# MySens-easyRS485-v001.net
KiCad netlist of a schematic drawn in EAGLE
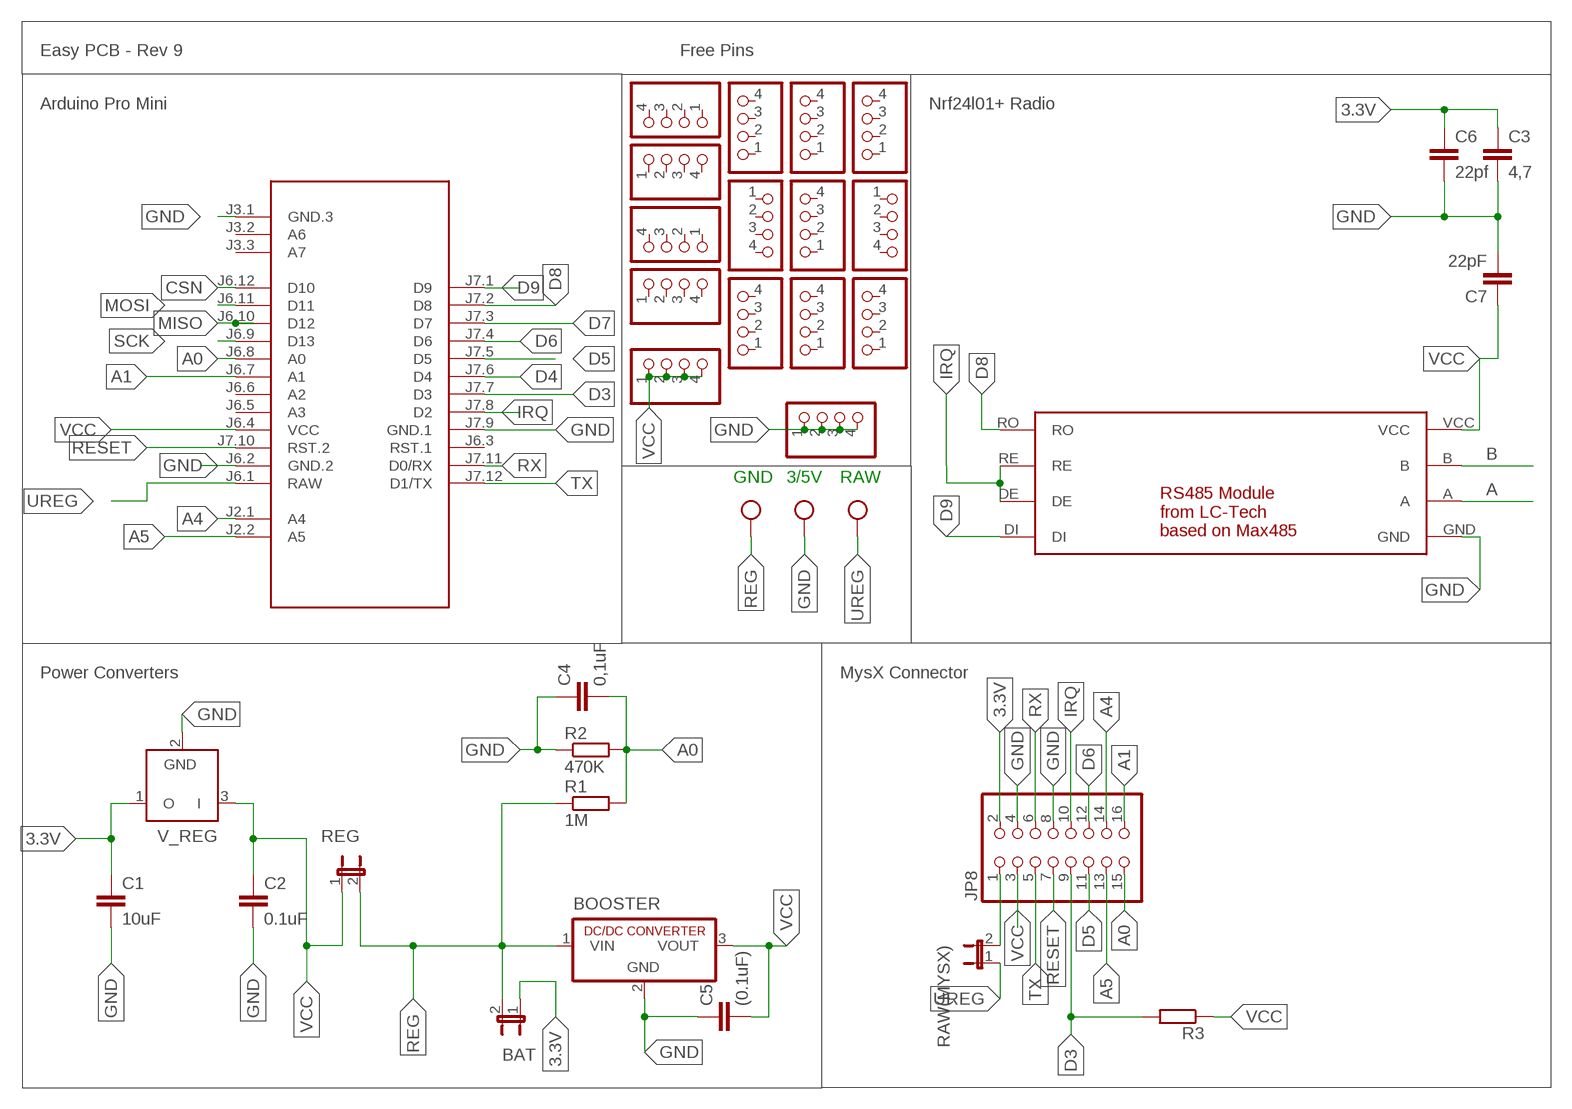
[diagram p0: schematic, sheet 1]

(export (version "E")
  (design (tool "Eeschema 10.0.6"))
  (components
    (comp (ref ".")
      (value "W237-103")
      (footprint "eagle-import:W237-103")
      (fields (field (name "MPN") "237-103"))
      (libsource (lib "eagle-import") (part "W237-103"))
    )
    (comp (ref "BAT")
      (value "JP1E")
      (footprint "eagle-import:JP1")
      (libsource (lib "eagle-import") (part "JP1E"))
    )
    (comp (ref "BOOSTER")
      (value "R-78C1.8-1.0")
      (footprint "eagle-import:SIP3")
      (libsource (lib "eagle-import") (part "R-78C-1.01.8"))
    )
    (comp (ref "C1")
      (value "10uF")
      (footprint "eagle-import:C5B2.5")
      (libsource (lib "eagle-import") (part "C5/2.5"))
    )
    (comp (ref "C2")
      (value "0.1uF")
      (footprint "eagle-import:C5B2.5")
      (libsource (lib "eagle-import") (part "C5/2.5"))
    )
    (comp (ref "C3")
      (value "4,7")
      (footprint "eagle-import:C5B2.5")
      (libsource (lib "eagle-import") (part "C5/2.5"))
    )
    (comp (ref "C4")
      (value "0,1uF")
      (footprint "eagle-import:C5B2.5")
      (libsource (lib "eagle-import") (part "C5/2.5"))
    )
    (comp (ref "C5")
      (value "(0.1uF)")
      (footprint "eagle-import:C5B2.5")
      (libsource (lib "eagle-import") (part "C5/2.5"))
    )
    (comp (ref "C6")
      (value "22pf")
      (footprint "eagle-import:C0805")
      (libsource (lib "eagle-import") (part "C-EUC0805"))
    )
    (comp (ref "C7")
      (value "22pF")
      (footprint "eagle-import:C0805")
      (libsource (lib "eagle-import") (part "C-EUC0805"))
    )
    (comp (ref "JP1")
      (value "PINHD-1X04_2.54-S")
      (footprint "eagle-import:1X04-S")
      (libsource (lib "eagle-import") (part "PINHD-1X04_2.54-S"))
    )
    (comp (ref "JP2")
      (value "PINHD-1X04_2.54-S")
      (footprint "eagle-import:1X04-S")
      (libsource (lib "eagle-import") (part "PINHD-1X04_2.54-S"))
    )
    (comp (ref "JP3")
      (value "PINHD-1X04_2.54-S")
      (footprint "eagle-import:1X04-S")
      (libsource (lib "eagle-import") (part "PINHD-1X04_2.54-S"))
    )
    (comp (ref "JP4")
      (value "PINHD-1X04_2.54-S")
      (footprint "eagle-import:1X04-S")
      (libsource (lib "eagle-import") (part "PINHD-1X04_2.54-S"))
    )
    (comp (ref "JP5")
      (value "PINHD-1X04_2.54-S")
      (footprint "eagle-import:1X04-S")
      (libsource (lib "eagle-import") (part "PINHD-1X04_2.54-S"))
    )
    (comp (ref "JP6")
      (value "PINHD-1X04_2.54-S")
      (footprint "eagle-import:1X04-S")
      (libsource (lib "eagle-import") (part "PINHD-1X04_2.54-S"))
    )
    (comp (ref "JP7")
      (value "PINHD-1X04_2.54-S")
      (footprint "eagle-import:1X04-S")
      (libsource (lib "eagle-import") (part "PINHD-1X04_2.54-S"))
    )
    (comp (ref "JP8")
      (value "PINHD-2X08_2.54")
      (footprint "eagle-import:2X08")
      (libsource (lib "eagle-import") (part "PINHD-2X08_2.54"))
    )
    (comp (ref "JP9")
      (value "PINHD-1X04_2.54-S")
      (footprint "eagle-import:1X04-S")
      (libsource (lib "eagle-import") (part "PINHD-1X04_2.54-S"))
    )
    (comp (ref "JP10")
      (value "PINHD-1X04_2.54-S")
      (footprint "eagle-import:1X04-S")
      (libsource (lib "eagle-import") (part "PINHD-1X04_2.54-S"))
    )
    (comp (ref "JP11")
      (value "PINHD-1X04_2.54-S")
      (footprint "eagle-import:1X04-S")
      (libsource (lib "eagle-import") (part "PINHD-1X04_2.54-S"))
    )
    (comp (ref "JP12")
      (value "PINHD-1X04_2.54-S")
      (footprint "eagle-import:1X04-S")
      (libsource (lib "eagle-import") (part "PINHD-1X04_2.54-S"))
    )
    (comp (ref "JP13")
      (value "PINHD-1X04_2.54-S")
      (footprint "eagle-import:1X04-S")
      (libsource (lib "eagle-import") (part "PINHD-1X04_2.54-S"))
    )
    (comp (ref "JP14")
      (value "PINHD-1X04_2.54-S")
      (footprint "eagle-import:1X04-S")
      (libsource (lib "eagle-import") (part "PINHD-1X04_2.54-S"))
    )
    (comp (ref "JP15")
      (value "PINHD-1X04_2.54-S")
      (footprint "eagle-import:1X04-S")
      (libsource (lib "eagle-import") (part "PINHD-1X04_2.54-S"))
    )
    (comp (ref "JP16")
      (value "PINHD-1X04_2.54-S")
      (footprint "eagle-import:1X04-S")
      (libsource (lib "eagle-import") (part "PINHD-1X04_2.54-S"))
    )
    (comp (ref "M1")
      (value "ARDUINO-PRO-MINI-3.3V#NP")
      (footprint "eagle-import:ARDUINO-PRO-MINI#NP")
      (libsource (lib "eagle-import") (part "ARDUINO-PRO-MINI-#NP3.3V"))
    )
    (comp (ref "R1")
      (value "1M")
      (footprint "eagle-import:0204_7")
      (libsource (lib "eagle-import") (part "R-EU_0204/7"))
    )
    (comp (ref "R2")
      (value "470K")
      (footprint "eagle-import:0204_7")
      (libsource (lib "eagle-import") (part "R-EU_0204/7"))
    )
    (comp (ref "R3")
      (value "R-EU_0204/7")
      (footprint "eagle-import:0204_7")
      (libsource (lib "eagle-import") (part "R-EU_0204/7"))
    )
    (comp (ref "RAW(MYSX)")
      (value "JP1E")
      (footprint "eagle-import:JP1")
      (libsource (lib "eagle-import") (part "JP1E"))
    )
    (comp (ref "REG")
      (value "JP1E")
      (footprint "eagle-import:JP1")
      (libsource (lib "eagle-import") (part "JP1E"))
    )
    (comp (ref "U$1")
      (value "RS485-LCTECH")
      (footprint "eagle-import:RS485-LCTECH")
      (libsource (lib "eagle-import") (part "RS485-LCTECH"))
    )
    (comp (ref "V_REG")
      (value "LP2950Z")
      (footprint "eagle-import:TO92")
      (libsource (lib "eagle-import") (part "LP2950Z"))
    )
  )
  (nets
    (net (code "1") (name "/A") (class "Default")
      (node (ref "U$1") (pin "A") (pinfunction "A_A") (pintype "bidirectional"))
    )
    (net (code "2") (name "/B") (class "Default")
      (node (ref "U$1") (pin "B") (pinfunction "B_B") (pintype "bidirectional"))
    )
    (net (code "3") (name "3.3V") (class "Default")
      (node (ref "BAT") (pin "1") (pinfunction "1_1") (pintype "passive"))
      (node (ref "C1") (pin "1") (pinfunction "1_1") (pintype "passive"))
      (node (ref "C3") (pin "1") (pinfunction "1_1") (pintype "passive"))
      (node (ref "C6") (pin "1") (pinfunction "1_1") (pintype "passive"))
      (node (ref "JP8") (pin "2") (pinfunction "2_2") (pintype "passive"))
      (node (ref "V_REG") (pin "1") (pinfunction "O_1") (pintype "input"))
    )
    (net (code "4") (name "A0") (class "Default")
      (node (ref "C4") (pin "2") (pinfunction "2_2") (pintype "passive"))
      (node (ref "JP8") (pin "15") (pinfunction "15_15") (pintype "passive"))
      (node (ref "M1") (pin "J6.8") (pinfunction "A0_J6.8") (pintype "bidirectional"))
      (node (ref "R1") (pin "2") (pinfunction "2_2") (pintype "passive"))
      (node (ref "R2") (pin "2") (pinfunction "2_2") (pintype "passive"))
    )
    (net (code "5") (name "A1") (class "Default")
      (node (ref "JP8") (pin "16") (pinfunction "16_16") (pintype "passive"))
      (node (ref "M1") (pin "J6.7") (pinfunction "A1_J6.7") (pintype "bidirectional"))
    )
    (net (code "6") (name "A4") (class "Default")
      (node (ref "JP8") (pin "14") (pinfunction "14_14") (pintype "passive"))
      (node (ref "M1") (pin "J2.1") (pinfunction "A4_J2.1") (pintype "bidirectional"))
    )
    (net (code "7") (name "A5") (class "Default")
      (node (ref "JP8") (pin "13") (pinfunction "13_13") (pintype "passive"))
      (node (ref "M1") (pin "J2.2") (pinfunction "A5_J2.2") (pintype "bidirectional"))
    )
    (net (code "8") (name "CSN") (class "Default")
      (node (ref "M1") (pin "J6.12") (pinfunction "D10_J6.12") (pintype "bidirectional"))
    )
    (net (code "9") (name "D3") (class "Default")
      (node (ref "JP8") (pin "9") (pinfunction "9_9") (pintype "passive"))
      (node (ref "M1") (pin "J7.7") (pinfunction "D3_J7.7") (pintype "bidirectional"))
      (node (ref "R3") (pin "2") (pinfunction "2_2") (pintype "passive"))
    )
    (net (code "10") (name "D4") (class "Default")
      (node (ref "M1") (pin "J7.6") (pinfunction "D4_J7.6") (pintype "bidirectional"))
    )
    (net (code "11") (name "D5") (class "Default")
      (node (ref "JP8") (pin "11") (pinfunction "11_11") (pintype "passive"))
      (node (ref "M1") (pin "J7.5") (pinfunction "D5_J7.5") (pintype "bidirectional"))
    )
    (net (code "12") (name "D6") (class "Default")
      (node (ref "JP8") (pin "12") (pinfunction "12_12") (pintype "passive"))
      (node (ref "M1") (pin "J7.4") (pinfunction "D6_J7.4") (pintype "bidirectional"))
    )
    (net (code "13") (name "D7") (class "Default")
      (node (ref "M1") (pin "J7.3") (pinfunction "D7_J7.3") (pintype "bidirectional"))
    )
    (net (code "14") (name "D8") (class "Default")
      (node (ref "M1") (pin "J7.2") (pinfunction "D8_J7.2") (pintype "bidirectional"))
      (node (ref "U$1") (pin "RO") (pinfunction "RO_RO") (pintype "bidirectional"))
    )
    (net (code "15") (name "D9") (class "Default")
      (node (ref "M1") (pin "J7.1") (pinfunction "D9_J7.1") (pintype "bidirectional"))
      (node (ref "U$1") (pin "DI") (pinfunction "DI_DI") (pintype "bidirectional"))
    )
    (net (code "16") (name "GND") (class "Default")
      (node (ref ".") (pin "2") (pinfunction "KL_2") (pintype "passive"))
      (node (ref "BOOSTER") (pin "2") (pinfunction "GND_2") (pintype "passive"))
      (node (ref "C1") (pin "2") (pinfunction "2_2") (pintype "passive"))
      (node (ref "C2") (pin "2") (pinfunction "2_2") (pintype "passive"))
      (node (ref "C3") (pin "2") (pinfunction "2_2") (pintype "passive"))
      (node (ref "C4") (pin "1") (pinfunction "1_1") (pintype "passive"))
      (node (ref "C5") (pin "1") (pinfunction "1_1") (pintype "passive"))
      (node (ref "C6") (pin "2") (pinfunction "2_2") (pintype "passive"))
      (node (ref "C7") (pin "2") (pinfunction "2_2") (pintype "passive"))
      (node (ref "JP1") (pin "1") (pinfunction "1_1") (pintype "passive"))
      (node (ref "JP1") (pin "2") (pinfunction "2_2") (pintype "passive"))
      (node (ref "JP1") (pin "3") (pinfunction "3_3") (pintype "passive"))
      (node (ref "JP1") (pin "4") (pinfunction "4_4") (pintype "passive"))
      (node (ref "JP8") (pin "4") (pinfunction "4_4") (pintype "passive"))
      (node (ref "JP8") (pin "8") (pinfunction "8_8") (pintype "passive"))
      (node (ref "M1") (pin "J3.1") (pinfunction "GND.3_J3.1") (pintype "bidirectional"))
      (node (ref "M1") (pin "J6.2") (pinfunction "GND.2_J6.2") (pintype "power_in"))
      (node (ref "M1") (pin "J7.9") (pinfunction "GND.1_J7.9") (pintype "power_in"))
      (node (ref "R2") (pin "1") (pinfunction "1_1") (pintype "passive"))
      (node (ref "U$1") (pin "GND") (pinfunction "GND_GND") (pintype "bidirectional"))
      (node (ref "V_REG") (pin "2") (pinfunction "GND_2") (pintype "power_in"))
    )
    (net (code "17") (name "IRQ") (class "Default")
      (node (ref "JP8") (pin "10") (pinfunction "10_10") (pintype "passive"))
      (node (ref "M1") (pin "J7.8") (pinfunction "D2_J7.8") (pintype "bidirectional"))
      (node (ref "U$1") (pin "DE") (pinfunction "DE_DE") (pintype "bidirectional"))
      (node (ref "U$1") (pin "RE") (pinfunction "RE_RE") (pintype "bidirectional"))
    )
    (net (code "18") (name "MISO") (class "Default")
      (node (ref "M1") (pin "J6.10") (pinfunction "D12_J6.10") (pintype "bidirectional"))
    )
    (net (code "19") (name "MOSI") (class "Default")
      (node (ref "M1") (pin "J6.11") (pinfunction "D11_J6.11") (pintype "bidirectional"))
    )
    (net (code "20") (name "Net-(JP8-Pad1)") (class "Default")
      (node (ref "JP8") (pin "1") (pinfunction "1_1") (pintype "passive"))
      (node (ref "RAW(MYSX)") (pin "2") (pinfunction "2_2") (pintype "passive"))
    )
    (net (code "21") (name "REG") (class "Default")
      (node (ref ".") (pin "3") (pinfunction "KL_3") (pintype "passive"))
      (node (ref "BAT") (pin "2") (pinfunction "2_2") (pintype "passive"))
      (node (ref "BOOSTER") (pin "1") (pinfunction "VIN_1") (pintype "passive"))
      (node (ref "R1") (pin "1") (pinfunction "1_1") (pintype "passive"))
      (node (ref "REG") (pin "2") (pinfunction "2_2") (pintype "passive"))
    )
    (net (code "22") (name "RESET") (class "Default")
      (node (ref "JP8") (pin "7") (pinfunction "7_7") (pintype "passive"))
      (node (ref "M1") (pin "J7.10") (pinfunction "RST.2_J7.10") (pintype "bidirectional"))
    )
    (net (code "23") (name "RX") (class "Default")
      (node (ref "JP8") (pin "6") (pinfunction "6_6") (pintype "passive"))
      (node (ref "M1") (pin "J7.11") (pinfunction "D0/RX_J7.11") (pintype "bidirectional"))
    )
    (net (code "24") (name "SCK") (class "Default")
      (node (ref "M1") (pin "J6.9") (pinfunction "D13_J6.9") (pintype "bidirectional"))
    )
    (net (code "25") (name "TX") (class "Default")
      (node (ref "JP8") (pin "5") (pinfunction "5_5") (pintype "passive"))
      (node (ref "M1") (pin "J7.12") (pinfunction "D1/TX_J7.12") (pintype "bidirectional"))
    )
    (net (code "26") (name "UREG") (class "Default")
      (node (ref ".") (pin "1") (pinfunction "KL_1") (pintype "passive"))
      (node (ref "M1") (pin "J6.1") (pinfunction "RAW_J6.1") (pintype "power_in"))
      (node (ref "RAW(MYSX)") (pin "1") (pinfunction "1_1") (pintype "passive"))
    )
    (net (code "27") (name "VCC") (class "Default")
      (node (ref "BOOSTER") (pin "3") (pinfunction "VOUT_3") (pintype "passive"))
      (node (ref "C2") (pin "1") (pinfunction "1_1") (pintype "passive"))
      (node (ref "C5") (pin "2") (pinfunction "2_2") (pintype "passive"))
      (node (ref "C7") (pin "1") (pinfunction "1_1") (pintype "passive"))
      (node (ref "JP3") (pin "1") (pinfunction "1_1") (pintype "passive"))
      (node (ref "JP3") (pin "2") (pinfunction "2_2") (pintype "passive"))
      (node (ref "JP3") (pin "3") (pinfunction "3_3") (pintype "passive"))
      (node (ref "JP3") (pin "4") (pinfunction "4_4") (pintype "passive"))
      (node (ref "JP8") (pin "3") (pinfunction "3_3") (pintype "passive"))
      (node (ref "M1") (pin "J6.4") (pinfunction "VCC_J6.4") (pintype "power_in"))
      (node (ref "R3") (pin "1") (pinfunction "1_1") (pintype "passive"))
      (node (ref "REG") (pin "1") (pinfunction "1_1") (pintype "passive"))
      (node (ref "U$1") (pin "VCC") (pinfunction "VCC_VCC") (pintype "bidirectional"))
      (node (ref "V_REG") (pin "3") (pinfunction "I_3") (pintype "input"))
    )
    (net (code "28") (name "unconnected-(JP2-Pad1)") (class "Default")
      (node (ref "JP2") (pin "1") (pinfunction "1_1") (pintype "passive"))
    )
    (net (code "29") (name "unconnected-(JP2-Pad2)") (class "Default")
      (node (ref "JP2") (pin "2") (pinfunction "2_2") (pintype "passive"))
    )
    (net (code "30") (name "unconnected-(JP2-Pad3)") (class "Default")
      (node (ref "JP2") (pin "3") (pinfunction "3_3") (pintype "passive"))
    )
    (net (code "31") (name "unconnected-(JP2-Pad4)") (class "Default")
      (node (ref "JP2") (pin "4") (pinfunction "4_4") (pintype "passive"))
    )
    (net (code "32") (name "unconnected-(JP4-Pad1)") (class "Default")
      (node (ref "JP4") (pin "1") (pinfunction "1_1") (pintype "passive"))
    )
    (net (code "33") (name "unconnected-(JP4-Pad2)") (class "Default")
      (node (ref "JP4") (pin "2") (pinfunction "2_2") (pintype "passive"))
    )
    (net (code "34") (name "unconnected-(JP4-Pad3)") (class "Default")
      (node (ref "JP4") (pin "3") (pinfunction "3_3") (pintype "passive"))
    )
    (net (code "35") (name "unconnected-(JP4-Pad4)") (class "Default")
      (node (ref "JP4") (pin "4") (pinfunction "4_4") (pintype "passive"))
    )
    (net (code "36") (name "unconnected-(JP5-Pad1)") (class "Default")
      (node (ref "JP5") (pin "1") (pinfunction "1_1") (pintype "passive"))
    )
    (net (code "37") (name "unconnected-(JP5-Pad2)") (class "Default")
      (node (ref "JP5") (pin "2") (pinfunction "2_2") (pintype "passive"))
    )
    (net (code "38") (name "unconnected-(JP5-Pad3)") (class "Default")
      (node (ref "JP5") (pin "3") (pinfunction "3_3") (pintype "passive"))
    )
    (net (code "39") (name "unconnected-(JP5-Pad4)") (class "Default")
      (node (ref "JP5") (pin "4") (pinfunction "4_4") (pintype "passive"))
    )
    (net (code "40") (name "unconnected-(JP6-Pad1)") (class "Default")
      (node (ref "JP6") (pin "1") (pinfunction "1_1") (pintype "passive"))
    )
    (net (code "41") (name "unconnected-(JP6-Pad2)") (class "Default")
      (node (ref "JP6") (pin "2") (pinfunction "2_2") (pintype "passive"))
    )
    (net (code "42") (name "unconnected-(JP6-Pad3)") (class "Default")
      (node (ref "JP6") (pin "3") (pinfunction "3_3") (pintype "passive"))
    )
    (net (code "43") (name "unconnected-(JP6-Pad4)") (class "Default")
      (node (ref "JP6") (pin "4") (pinfunction "4_4") (pintype "passive"))
    )
    (net (code "44") (name "unconnected-(JP7-Pad1)") (class "Default")
      (node (ref "JP7") (pin "1") (pinfunction "1_1") (pintype "passive"))
    )
    (net (code "45") (name "unconnected-(JP7-Pad2)") (class "Default")
      (node (ref "JP7") (pin "2") (pinfunction "2_2") (pintype "passive"))
    )
    (net (code "46") (name "unconnected-(JP7-Pad3)") (class "Default")
      (node (ref "JP7") (pin "3") (pinfunction "3_3") (pintype "passive"))
    )
    (net (code "47") (name "unconnected-(JP7-Pad4)") (class "Default")
      (node (ref "JP7") (pin "4") (pinfunction "4_4") (pintype "passive"))
    )
    (net (code "48") (name "unconnected-(JP9-Pad1)") (class "Default")
      (node (ref "JP9") (pin "1") (pinfunction "1_1") (pintype "passive"))
    )
    (net (code "49") (name "unconnected-(JP9-Pad2)") (class "Default")
      (node (ref "JP9") (pin "2") (pinfunction "2_2") (pintype "passive"))
    )
    (net (code "50") (name "unconnected-(JP9-Pad3)") (class "Default")
      (node (ref "JP9") (pin "3") (pinfunction "3_3") (pintype "passive"))
    )
    (net (code "51") (name "unconnected-(JP9-Pad4)") (class "Default")
      (node (ref "JP9") (pin "4") (pinfunction "4_4") (pintype "passive"))
    )
    (net (code "52") (name "unconnected-(JP10-Pad1)") (class "Default")
      (node (ref "JP10") (pin "1") (pinfunction "1_1") (pintype "passive"))
    )
    (net (code "53") (name "unconnected-(JP10-Pad2)") (class "Default")
      (node (ref "JP10") (pin "2") (pinfunction "2_2") (pintype "passive"))
    )
    (net (code "54") (name "unconnected-(JP10-Pad3)") (class "Default")
      (node (ref "JP10") (pin "3") (pinfunction "3_3") (pintype "passive"))
    )
    (net (code "55") (name "unconnected-(JP10-Pad4)") (class "Default")
      (node (ref "JP10") (pin "4") (pinfunction "4_4") (pintype "passive"))
    )
    (net (code "56") (name "unconnected-(JP11-Pad1)") (class "Default")
      (node (ref "JP11") (pin "1") (pinfunction "1_1") (pintype "passive"))
    )
    (net (code "57") (name "unconnected-(JP11-Pad2)") (class "Default")
      (node (ref "JP11") (pin "2") (pinfunction "2_2") (pintype "passive"))
    )
    (net (code "58") (name "unconnected-(JP11-Pad3)") (class "Default")
      (node (ref "JP11") (pin "3") (pinfunction "3_3") (pintype "passive"))
    )
    (net (code "59") (name "unconnected-(JP11-Pad4)") (class "Default")
      (node (ref "JP11") (pin "4") (pinfunction "4_4") (pintype "passive"))
    )
    (net (code "60") (name "unconnected-(JP12-Pad1)") (class "Default")
      (node (ref "JP12") (pin "1") (pinfunction "1_1") (pintype "passive"))
    )
    (net (code "61") (name "unconnected-(JP12-Pad2)") (class "Default")
      (node (ref "JP12") (pin "2") (pinfunction "2_2") (pintype "passive"))
    )
    (net (code "62") (name "unconnected-(JP12-Pad3)") (class "Default")
      (node (ref "JP12") (pin "3") (pinfunction "3_3") (pintype "passive"))
    )
    (net (code "63") (name "unconnected-(JP12-Pad4)") (class "Default")
      (node (ref "JP12") (pin "4") (pinfunction "4_4") (pintype "passive"))
    )
    (net (code "64") (name "unconnected-(JP13-Pad1)") (class "Default")
      (node (ref "JP13") (pin "1") (pinfunction "1_1") (pintype "passive"))
    )
    (net (code "65") (name "unconnected-(JP13-Pad2)") (class "Default")
      (node (ref "JP13") (pin "2") (pinfunction "2_2") (pintype "passive"))
    )
    (net (code "66") (name "unconnected-(JP13-Pad3)") (class "Default")
      (node (ref "JP13") (pin "3") (pinfunction "3_3") (pintype "passive"))
    )
    (net (code "67") (name "unconnected-(JP13-Pad4)") (class "Default")
      (node (ref "JP13") (pin "4") (pinfunction "4_4") (pintype "passive"))
    )
    (net (code "68") (name "unconnected-(JP14-Pad1)") (class "Default")
      (node (ref "JP14") (pin "1") (pinfunction "1_1") (pintype "passive"))
    )
    (net (code "69") (name "unconnected-(JP14-Pad2)") (class "Default")
      (node (ref "JP14") (pin "2") (pinfunction "2_2") (pintype "passive"))
    )
    (net (code "70") (name "unconnected-(JP14-Pad3)") (class "Default")
      (node (ref "JP14") (pin "3") (pinfunction "3_3") (pintype "passive"))
    )
    (net (code "71") (name "unconnected-(JP14-Pad4)") (class "Default")
      (node (ref "JP14") (pin "4") (pinfunction "4_4") (pintype "passive"))
    )
    (net (code "72") (name "unconnected-(JP15-Pad1)") (class "Default")
      (node (ref "JP15") (pin "1") (pinfunction "1_1") (pintype "passive"))
    )
    (net (code "73") (name "unconnected-(JP15-Pad2)") (class "Default")
      (node (ref "JP15") (pin "2") (pinfunction "2_2") (pintype "passive"))
    )
    (net (code "74") (name "unconnected-(JP15-Pad3)") (class "Default")
      (node (ref "JP15") (pin "3") (pinfunction "3_3") (pintype "passive"))
    )
    (net (code "75") (name "unconnected-(JP15-Pad4)") (class "Default")
      (node (ref "JP15") (pin "4") (pinfunction "4_4") (pintype "passive"))
    )
    (net (code "76") (name "unconnected-(JP16-Pad1)") (class "Default")
      (node (ref "JP16") (pin "1") (pinfunction "1_1") (pintype "passive"))
    )
    (net (code "77") (name "unconnected-(JP16-Pad2)") (class "Default")
      (node (ref "JP16") (pin "2") (pinfunction "2_2") (pintype "passive"))
    )
    (net (code "78") (name "unconnected-(JP16-Pad3)") (class "Default")
      (node (ref "JP16") (pin "3") (pinfunction "3_3") (pintype "passive"))
    )
    (net (code "79") (name "unconnected-(JP16-Pad4)") (class "Default")
      (node (ref "JP16") (pin "4") (pinfunction "4_4") (pintype "passive"))
    )
    (net (code "80") (name "unconnected-(M1-A2-PadJ6.6)") (class "Default")
      (node (ref "M1") (pin "J6.6") (pinfunction "A2_J6.6") (pintype "bidirectional"))
    )
    (net (code "81") (name "unconnected-(M1-A3-PadJ6.5)") (class "Default")
      (node (ref "M1") (pin "J6.5") (pinfunction "A3_J6.5") (pintype "bidirectional"))
    )
    (net (code "82") (name "unconnected-(M1-A6-PadJ3.2)") (class "Default")
      (node (ref "M1") (pin "J3.2") (pinfunction "A6_J3.2") (pintype "bidirectional"))
    )
    (net (code "83") (name "unconnected-(M1-A7-PadJ3.3)") (class "Default")
      (node (ref "M1") (pin "J3.3") (pinfunction "A7_J3.3") (pintype "bidirectional"))
    )
    (net (code "84") (name "unconnected-(M1-RST.1-PadJ6.3)") (class "Default")
      (node (ref "M1") (pin "J6.3") (pinfunction "RST.1_J6.3") (pintype "bidirectional"))
    )
  )
)
